# TRV_MRF49_U.net
KiCad netlist of a schematic drawn in EAGLE
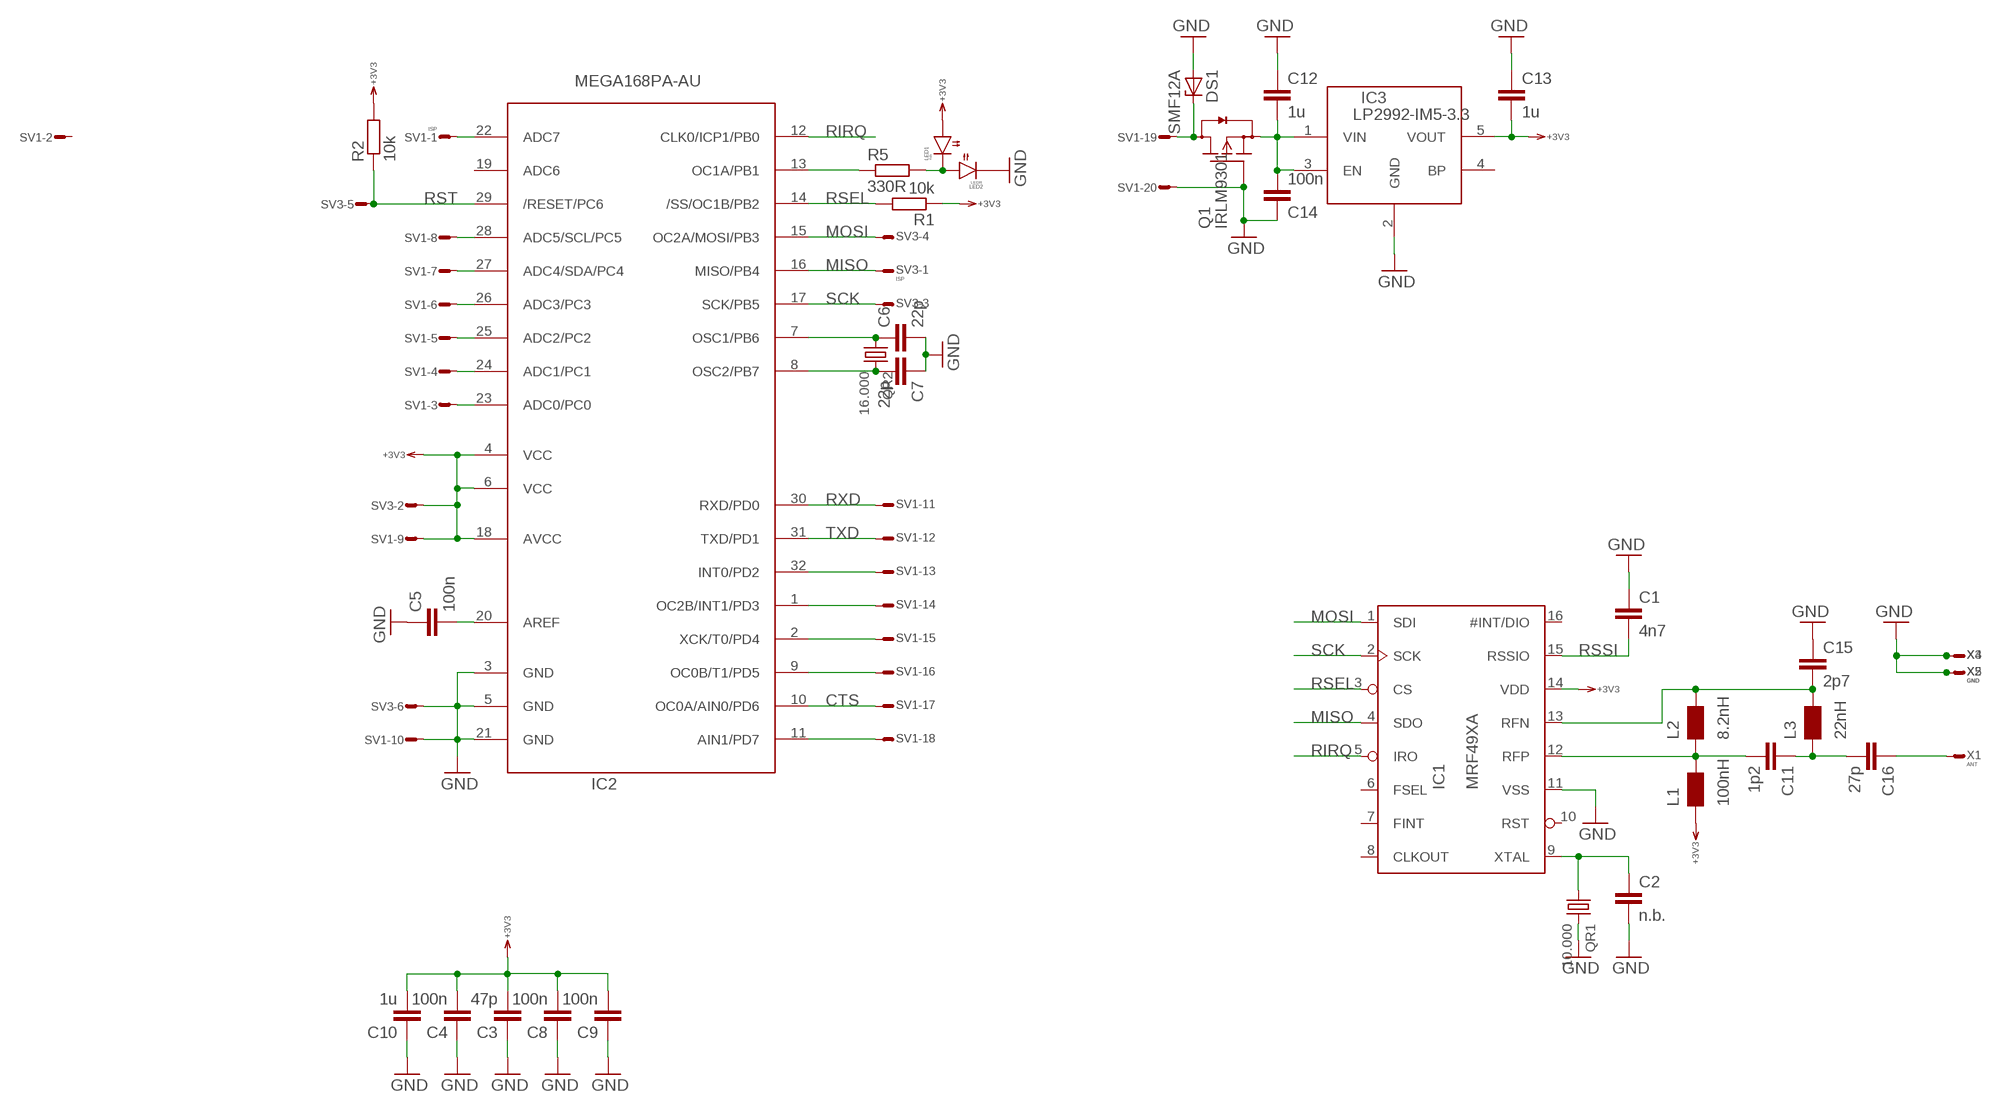
[diagram p0: schematic, sheet 1]

(export (version "E")
  (design (tool "Eeschema 10.0.6"))
  (components
    (comp (ref "C1")
      (value "4n7")
      (footprint "eagle-import:0603")
      (libsource (lib "eagle-import") (part "C0603"))
    )
    (comp (ref "C2")
      (value "n.b.")
      (footprint "eagle-import:0603")
      (libsource (lib "eagle-import") (part "C0603"))
    )
    (comp (ref "C3")
      (value "47p")
      (footprint "eagle-import:0603")
      (libsource (lib "eagle-import") (part "C0603"))
    )
    (comp (ref "C4")
      (value "100n")
      (footprint "eagle-import:0603")
      (libsource (lib "eagle-import") (part "C0603"))
    )
    (comp (ref "C5")
      (value "100n")
      (footprint "eagle-import:0603")
      (libsource (lib "eagle-import") (part "C0603"))
    )
    (comp (ref "C6")
      (value "22p")
      (footprint "eagle-import:0603")
      (libsource (lib "eagle-import") (part "C0603"))
    )
    (comp (ref "C7")
      (value "22p")
      (footprint "eagle-import:0603")
      (libsource (lib "eagle-import") (part "C0603"))
    )
    (comp (ref "C8")
      (value "100n")
      (footprint "eagle-import:0603")
      (libsource (lib "eagle-import") (part "C0603"))
    )
    (comp (ref "C9")
      (value "100n")
      (footprint "eagle-import:0603")
      (libsource (lib "eagle-import") (part "C0603"))
    )
    (comp (ref "C10")
      (value "1u")
      (footprint "eagle-import:0603")
      (libsource (lib "eagle-import") (part "C0603"))
    )
    (comp (ref "C11")
      (value "1p2")
      (footprint "eagle-import:0603")
      (libsource (lib "eagle-import") (part "C0603"))
    )
    (comp (ref "C12")
      (value "1u")
      (footprint "eagle-import:0603")
      (libsource (lib "eagle-import") (part "C0603"))
    )
    (comp (ref "C13")
      (value "1u")
      (footprint "eagle-import:0603")
      (libsource (lib "eagle-import") (part "C0603"))
    )
    (comp (ref "C14")
      (value "100n")
      (footprint "eagle-import:0603")
      (libsource (lib "eagle-import") (part "C0603"))
    )
    (comp (ref "C15")
      (value "2p7")
      (footprint "eagle-import:0603")
      (libsource (lib "eagle-import") (part "C0603"))
    )
    (comp (ref "C16")
      (value "27p")
      (footprint "eagle-import:0603")
      (libsource (lib "eagle-import") (part "C0603"))
    )
    (comp (ref "DS1")
      (value "SMF12A")
      (footprint "eagle-import:SMF")
      (libsource (lib "eagle-import") (part "TVS-DSMF"))
    )
    (comp (ref "IC1")
      (value "MRF49XA")
      (footprint "eagle-import:TSSOP16")
      (libsource (lib "eagle-import") (part "MRF49XA"))
    )
    (comp (ref "IC2")
      (value "MEGA168PA-AU")
      (footprint "eagle-import:TQFP32-08")
      (libsource (lib "eagle-import") (part "MEGA168PA"))
    )
    (comp (ref "IC3")
      (value "LP2992-IM5-3.3")
      (footprint "eagle-import:SOT23-5")
      (libsource (lib "eagle-import") (part "LDO"))
    )
    (comp (ref "L1")
      (value "100nH")
      (footprint "eagle-import:0603")
      (libsource (lib "eagle-import") (part "L0603"))
    )
    (comp (ref "L2")
      (value "8.2nH")
      (footprint "eagle-import:0603")
      (libsource (lib "eagle-import") (part "L0603"))
    )
    (comp (ref "L3")
      (value "22nH")
      (footprint "eagle-import:0603")
      (libsource (lib "eagle-import") (part "L0603"))
    )
    (comp (ref "LED1")
      (value "n.b.")
      (footprint "eagle-import:0603")
      (libsource (lib "eagle-import") (part "LED0603"))
    )
    (comp (ref "LED2")
      (value "LEDR")
      (footprint "eagle-import:0603")
      (libsource (lib "eagle-import") (part "LED0603"))
    )
    (comp (ref "Q1")
      (value "IRLM9301")
      (footprint "eagle-import:SOT23")
      (libsource (lib "eagle-import") (part "FET-PDSOT23"))
    )
    (comp (ref "QR1")
      (value "10.000")
      (footprint "eagle-import:HC49U-V")
      (libsource (lib "eagle-import") (part "Q49UV"))
    )
    (comp (ref "QR2")
      (value "16.000")
      (footprint "eagle-import:HC49U-V")
      (libsource (lib "eagle-import") (part "Q49UV"))
    )
    (comp (ref "R1")
      (value "10k")
      (footprint "eagle-import:0603")
      (libsource (lib "eagle-import") (part "R0603"))
    )
    (comp (ref "R2")
      (value "10k")
      (footprint "eagle-import:0603")
      (libsource (lib "eagle-import") (part "R0603"))
    )
    (comp (ref "R5")
      (value "330R")
      (footprint "eagle-import:0603")
      (libsource (lib "eagle-import") (part "R0603"))
    )
    (comp (ref "SV1")
      (value "ISP")
      (footprint "eagle-import:ML20")
      (libsource (lib "eagle-import") (part "ML20?E"))
    )
    (comp (ref "SV3")
      (value "ISP")
      (footprint "eagle-import:ML6")
      (libsource (lib "eagle-import") (part "ML6E"))
    )
    (comp (ref "X1")
      (value "ANT")
      (footprint "eagle-import:S2.54_1.27")
      (libsource (lib "eagle-import") (part "WIREPADS2.54/1.27"))
    )
    (comp (ref "X2")
      (value "GND")
      (footprint "eagle-import:S2.54_1.27")
      (libsource (lib "eagle-import") (part "WIREPADS2.54/1.27"))
    )
    (comp (ref "X3")
      (value "WIREPADS2.54/1.27")
      (footprint "eagle-import:S2.54_1.27")
      (libsource (lib "eagle-import") (part "WIREPADS2.54/1.27"))
    )
    (comp (ref "X4")
      (value "WIREPADS2.54/1.27")
      (footprint "eagle-import:S2.54_1.27")
      (libsource (lib "eagle-import") (part "WIREPADS2.54/1.27"))
    )
    (comp (ref "X5")
      (value "GND")
      (footprint "eagle-import:S2.54_1.27")
      (libsource (lib "eagle-import") (part "WIREPADS2.54/1.27"))
    )
  )
  (nets
    (net (code "1") (name "+3V3") (class "Default")
      (node (ref "C10") (pin "2") (pinfunction "2_2") (pintype "passive"))
      (node (ref "C13") (pin "2") (pinfunction "2_2") (pintype "passive"))
      (node (ref "C3") (pin "2") (pinfunction "2_2") (pintype "passive"))
      (node (ref "C4") (pin "2") (pinfunction "2_2") (pintype "passive"))
      (node (ref "C8") (pin "2") (pinfunction "2_2") (pintype "passive"))
      (node (ref "C9") (pin "2") (pinfunction "2_2") (pintype "passive"))
      (node (ref "IC1") (pin "14") (pinfunction "VDD_14") (pintype "input"))
      (node (ref "IC2") (pin "18") (pinfunction "AVCC_18") (pintype "bidirectional"))
      (node (ref "IC2") (pin "4") (pinfunction "VCC_4") (pintype "bidirectional"))
      (node (ref "IC2") (pin "6") (pinfunction "VCC_6") (pintype "bidirectional"))
      (node (ref "IC3") (pin "5") (pinfunction "VOUT_5") (pintype "bidirectional"))
      (node (ref "L1") (pin "1") (pinfunction "1_1") (pintype "passive"))
      (node (ref "LED1") (pin "1") (pinfunction "A_1") (pintype "bidirectional"))
      (node (ref "R1") (pin "1") (pinfunction "1_1") (pintype "passive"))
      (node (ref "R2") (pin "2") (pinfunction "2_2") (pintype "passive"))
      (node (ref "SV1") (pin "9") (pinfunction "S_9") (pintype "passive"))
      (node (ref "SV3") (pin "2") (pinfunction "S_2") (pintype "passive"))
    )
    (net (code "2") (name "/CTS") (class "Default")
      (node (ref "IC2") (pin "10") (pinfunction "OC0A/AIN0/PD6_10") (pintype "bidirectional"))
      (node (ref "SV1") (pin "17") (pinfunction "S_17") (pintype "passive"))
    )
    (net (code "3") (name "/MISO") (class "Default")
      (node (ref "IC1") (pin "4") (pinfunction "SDO_4") (pintype "output"))
      (node (ref "IC2") (pin "16") (pinfunction "MISO/PB4_16") (pintype "bidirectional"))
      (node (ref "SV3") (pin "1") (pinfunction "S_1") (pintype "passive"))
    )
    (net (code "4") (name "/MOSI") (class "Default")
      (node (ref "IC1") (pin "1") (pinfunction "SDI_1") (pintype "input"))
      (node (ref "IC2") (pin "15") (pinfunction "OC2A/MOSI/PB3_15") (pintype "bidirectional"))
      (node (ref "SV3") (pin "4") (pinfunction "S_4") (pintype "passive"))
    )
    (net (code "5") (name "/RIRQ") (class "Default")
      (node (ref "IC1") (pin "5") (pinfunction "IRO_5") (pintype "output"))
      (node (ref "IC2") (pin "12") (pinfunction "CLK0/ICP1/PB0_12") (pintype "bidirectional"))
    )
    (net (code "6") (name "/RSEL") (class "Default")
      (node (ref "IC1") (pin "3") (pinfunction "CS_3") (pintype "input"))
      (node (ref "IC2") (pin "14") (pinfunction "/SS/OC1B/PB2_14") (pintype "bidirectional"))
      (node (ref "R1") (pin "2") (pinfunction "2_2") (pintype "passive"))
    )
    (net (code "7") (name "/RSSI") (class "Default")
      (node (ref "C1") (pin "2") (pinfunction "2_2") (pintype "passive"))
      (node (ref "IC1") (pin "15") (pinfunction "RSSIO_15") (pintype "bidirectional"))
    )
    (net (code "8") (name "/RST") (class "Default")
      (node (ref "IC2") (pin "29") (pinfunction "/RESET/PC6_29") (pintype "bidirectional"))
      (node (ref "R2") (pin "1") (pinfunction "1_1") (pintype "passive"))
      (node (ref "SV3") (pin "5") (pinfunction "S_5") (pintype "passive"))
    )
    (net (code "9") (name "/RXD") (class "Default")
      (node (ref "IC2") (pin "30") (pinfunction "RXD/PD0_30") (pintype "bidirectional"))
      (node (ref "SV1") (pin "11") (pinfunction "S_11") (pintype "passive"))
    )
    (net (code "10") (name "/SCK") (class "Default")
      (node (ref "IC1") (pin "2") (pinfunction "SCK_2") (pintype "input"))
      (node (ref "IC2") (pin "17") (pinfunction "SCK/PB5_17") (pintype "bidirectional"))
      (node (ref "SV3") (pin "3") (pinfunction "S_3") (pintype "passive"))
    )
    (net (code "11") (name "/TXD") (class "Default")
      (node (ref "IC2") (pin "31") (pinfunction "TXD/PD1_31") (pintype "bidirectional"))
      (node (ref "SV1") (pin "12") (pinfunction "S_12") (pintype "passive"))
    )
    (net (code "12") (name "GND") (class "Default")
      (node (ref "C1") (pin "1") (pinfunction "1_1") (pintype "passive"))
      (node (ref "C10") (pin "1") (pinfunction "1_1") (pintype "passive"))
      (node (ref "C12") (pin "1") (pinfunction "1_1") (pintype "passive"))
      (node (ref "C13") (pin "1") (pinfunction "1_1") (pintype "passive"))
      (node (ref "C14") (pin "1") (pinfunction "1_1") (pintype "passive"))
      (node (ref "C15") (pin "1") (pinfunction "1_1") (pintype "passive"))
      (node (ref "C2") (pin "2") (pinfunction "2_2") (pintype "passive"))
      (node (ref "C3") (pin "1") (pinfunction "1_1") (pintype "passive"))
      (node (ref "C4") (pin "1") (pinfunction "1_1") (pintype "passive"))
      (node (ref "C5") (pin "1") (pinfunction "1_1") (pintype "passive"))
      (node (ref "C6") (pin "2") (pinfunction "2_2") (pintype "passive"))
      (node (ref "C7") (pin "1") (pinfunction "1_1") (pintype "passive"))
      (node (ref "C8") (pin "1") (pinfunction "1_1") (pintype "passive"))
      (node (ref "C9") (pin "1") (pinfunction "1_1") (pintype "passive"))
      (node (ref "DS1") (pin "A") (pinfunction "A_A") (pintype "passive"))
      (node (ref "IC1") (pin "11") (pinfunction "VSS_11") (pintype "input"))
      (node (ref "IC2") (pin "21") (pinfunction "GND_21") (pintype "bidirectional"))
      (node (ref "IC2") (pin "3") (pinfunction "GND_3") (pintype "bidirectional"))
      (node (ref "IC2") (pin "5") (pinfunction "GND_5") (pintype "bidirectional"))
      (node (ref "IC3") (pin "2") (pinfunction "GND_2") (pintype "bidirectional"))
      (node (ref "LED2") (pin "2") (pinfunction "C_2") (pintype "bidirectional"))
      (node (ref "Q1") (pin "1") (pinfunction "G_1") (pintype "passive"))
      (node (ref "QR1") (pin "2") (pinfunction "2_2") (pintype "passive"))
      (node (ref "SV1") (pin "10") (pinfunction "S_10") (pintype "passive"))
      (node (ref "SV1") (pin "20") (pinfunction "S_20") (pintype "passive"))
      (node (ref "SV3") (pin "6") (pinfunction "S_6") (pintype "passive"))
      (node (ref "X2") (pin "1") (pinfunction "S_1") (pintype "passive"))
      (node (ref "X3") (pin "1") (pinfunction "S_1") (pintype "passive"))
      (node (ref "X4") (pin "1") (pinfunction "S_1") (pintype "passive"))
      (node (ref "X5") (pin "1") (pinfunction "S_1") (pintype "passive"))
    )
    (net (code "13") (name "Net-(C11-Pad1)") (class "Default")
      (node (ref "C11") (pin "1") (pinfunction "1_1") (pintype "passive"))
      (node (ref "C16") (pin "2") (pinfunction "2_2") (pintype "passive"))
      (node (ref "L3") (pin "1") (pinfunction "1_1") (pintype "passive"))
    )
    (net (code "14") (name "Net-(IC1-RFN)") (class "Default")
      (node (ref "C15") (pin "2") (pinfunction "2_2") (pintype "passive"))
      (node (ref "IC1") (pin "13") (pinfunction "RFN_13") (pintype "bidirectional"))
      (node (ref "L2") (pin "2") (pinfunction "2_2") (pintype "passive"))
      (node (ref "L3") (pin "2") (pinfunction "2_2") (pintype "passive"))
    )
    (net (code "15") (name "Net-(IC1-RFP)") (class "Default")
      (node (ref "C11") (pin "2") (pinfunction "2_2") (pintype "passive"))
      (node (ref "IC1") (pin "12") (pinfunction "RFP_12") (pintype "bidirectional"))
      (node (ref "L1") (pin "2") (pinfunction "2_2") (pintype "passive"))
      (node (ref "L2") (pin "1") (pinfunction "1_1") (pintype "passive"))
    )
    (net (code "16") (name "Net-(IC1-XTAL)") (class "Default")
      (node (ref "C2") (pin "1") (pinfunction "1_1") (pintype "passive"))
      (node (ref "IC1") (pin "9") (pinfunction "XTAL_9") (pintype "input"))
      (node (ref "QR1") (pin "1") (pinfunction "1_1") (pintype "passive"))
    )
    (net (code "17") (name "Net-(IC2-ADC0{slash}PC0)") (class "Default")
      (node (ref "IC2") (pin "23") (pinfunction "ADC0/PC0_23") (pintype "bidirectional"))
      (node (ref "SV1") (pin "3") (pinfunction "S_3") (pintype "passive"))
    )
    (net (code "18") (name "Net-(IC2-ADC1{slash}PC1)") (class "Default")
      (node (ref "IC2") (pin "24") (pinfunction "ADC1/PC1_24") (pintype "bidirectional"))
      (node (ref "SV1") (pin "4") (pinfunction "S_4") (pintype "passive"))
    )
    (net (code "19") (name "Net-(IC2-ADC2{slash}PC2)") (class "Default")
      (node (ref "IC2") (pin "25") (pinfunction "ADC2/PC2_25") (pintype "bidirectional"))
      (node (ref "SV1") (pin "5") (pinfunction "S_5") (pintype "passive"))
    )
    (net (code "20") (name "Net-(IC2-ADC3{slash}PC3)") (class "Default")
      (node (ref "IC2") (pin "26") (pinfunction "ADC3/PC3_26") (pintype "bidirectional"))
      (node (ref "SV1") (pin "6") (pinfunction "S_6") (pintype "passive"))
    )
    (net (code "21") (name "Net-(IC2-ADC4{slash}SDA{slash}PC4)") (class "Default")
      (node (ref "IC2") (pin "27") (pinfunction "ADC4/SDA/PC4_27") (pintype "bidirectional"))
      (node (ref "SV1") (pin "7") (pinfunction "S_7") (pintype "passive"))
    )
    (net (code "22") (name "Net-(IC2-ADC5{slash}SCL{slash}PC5)") (class "Default")
      (node (ref "IC2") (pin "28") (pinfunction "ADC5/SCL/PC5_28") (pintype "bidirectional"))
      (node (ref "SV1") (pin "8") (pinfunction "S_8") (pintype "passive"))
    )
    (net (code "23") (name "Net-(IC2-ADC7)") (class "Default")
      (node (ref "IC2") (pin "22") (pinfunction "ADC7_22") (pintype "bidirectional"))
      (node (ref "SV1") (pin "1") (pinfunction "S_1") (pintype "passive"))
    )
    (net (code "24") (name "Net-(IC2-AIN1{slash}PD7)") (class "Default")
      (node (ref "IC2") (pin "11") (pinfunction "AIN1/PD7_11") (pintype "bidirectional"))
      (node (ref "SV1") (pin "18") (pinfunction "S_18") (pintype "passive"))
    )
    (net (code "25") (name "Net-(IC2-AREF)") (class "Default")
      (node (ref "C5") (pin "2") (pinfunction "2_2") (pintype "passive"))
      (node (ref "IC2") (pin "20") (pinfunction "AREF_20") (pintype "bidirectional"))
    )
    (net (code "26") (name "Net-(IC2-INT0{slash}PD2)") (class "Default")
      (node (ref "IC2") (pin "32") (pinfunction "INT0/PD2_32") (pintype "bidirectional"))
      (node (ref "SV1") (pin "13") (pinfunction "S_13") (pintype "passive"))
    )
    (net (code "27") (name "Net-(IC2-OC0B{slash}T1{slash}PD5)") (class "Default")
      (node (ref "IC2") (pin "9") (pinfunction "OC0B/T1/PD5_9") (pintype "bidirectional"))
      (node (ref "SV1") (pin "16") (pinfunction "S_16") (pintype "passive"))
    )
    (net (code "28") (name "Net-(IC2-OC1A{slash}PB1)") (class "Default")
      (node (ref "IC2") (pin "13") (pinfunction "OC1A/PB1_13") (pintype "bidirectional"))
      (node (ref "R5") (pin "1") (pinfunction "1_1") (pintype "passive"))
    )
    (net (code "29") (name "Net-(IC2-OC2B{slash}INT1{slash}PD3)") (class "Default")
      (node (ref "IC2") (pin "1") (pinfunction "OC2B/INT1/PD3_1") (pintype "bidirectional"))
      (node (ref "SV1") (pin "14") (pinfunction "S_14") (pintype "passive"))
    )
    (net (code "30") (name "Net-(IC2-OSC1{slash}PB6)") (class "Default")
      (node (ref "C6") (pin "1") (pinfunction "1_1") (pintype "passive"))
      (node (ref "IC2") (pin "7") (pinfunction "OSC1/PB6_7") (pintype "bidirectional"))
      (node (ref "QR2") (pin "1") (pinfunction "1_1") (pintype "passive"))
    )
    (net (code "31") (name "Net-(IC2-OSC2{slash}PB7)") (class "Default")
      (node (ref "C7") (pin "2") (pinfunction "2_2") (pintype "passive"))
      (node (ref "IC2") (pin "8") (pinfunction "OSC2/PB7_8") (pintype "bidirectional"))
      (node (ref "QR2") (pin "2") (pinfunction "2_2") (pintype "passive"))
    )
    (net (code "32") (name "Net-(IC2-XCK{slash}T0{slash}PD4)") (class "Default")
      (node (ref "IC2") (pin "2") (pinfunction "XCK/T0/PD4_2") (pintype "bidirectional"))
      (node (ref "SV1") (pin "15") (pinfunction "S_15") (pintype "passive"))
    )
    (net (code "33") (name "Net-(IC3-EN)") (class "Default")
      (node (ref "C12") (pin "2") (pinfunction "2_2") (pintype "passive"))
      (node (ref "C14") (pin "2") (pinfunction "2_2") (pintype "passive"))
      (node (ref "IC3") (pin "1") (pinfunction "VIN_1") (pintype "bidirectional"))
      (node (ref "IC3") (pin "3") (pinfunction "EN_3") (pintype "bidirectional"))
      (node (ref "Q1") (pin "2") (pinfunction "S_2") (pintype "passive"))
    )
    (net (code "34") (name "Net-(LED1-C)") (class "Default")
      (node (ref "LED1") (pin "2") (pinfunction "C_2") (pintype "bidirectional"))
      (node (ref "LED2") (pin "1") (pinfunction "A_1") (pintype "bidirectional"))
      (node (ref "R5") (pin "2") (pinfunction "2_2") (pintype "passive"))
    )
    (net (code "35") (name "Net-(Q1-D)") (class "Default")
      (node (ref "DS1") (pin "C") (pinfunction "C_C") (pintype "passive"))
      (node (ref "Q1") (pin "3") (pinfunction "D_3") (pintype "passive"))
      (node (ref "SV1") (pin "19") (pinfunction "S_19") (pintype "passive"))
    )
    (net (code "36") (name "Net-(X1-S)") (class "Default")
      (node (ref "C16") (pin "1") (pinfunction "1_1") (pintype "passive"))
      (node (ref "X1") (pin "1") (pinfunction "S_1") (pintype "passive"))
    )
    (net (code "37") (name "unconnected-(IC1-#INT{slash}DIO-Pad16)") (class "Default")
      (node (ref "IC1") (pin "16") (pinfunction "#INT/DIO_16") (pintype "bidirectional"))
    )
    (net (code "38") (name "unconnected-(IC1-CLKOUT-Pad8)") (class "Default")
      (node (ref "IC1") (pin "8") (pinfunction "CLKOUT_8") (pintype "output"))
    )
    (net (code "39") (name "unconnected-(IC1-FINT-Pad7)") (class "Default")
      (node (ref "IC1") (pin "7") (pinfunction "FINT_7") (pintype "bidirectional"))
    )
    (net (code "40") (name "unconnected-(IC1-FSEL-Pad6)") (class "Default")
      (node (ref "IC1") (pin "6") (pinfunction "FSEL_6") (pintype "bidirectional"))
    )
    (net (code "41") (name "unconnected-(IC1-RST-Pad10)") (class "Default")
      (node (ref "IC1") (pin "10") (pinfunction "RST_10") (pintype "bidirectional"))
    )
    (net (code "42") (name "unconnected-(IC2-ADC6-Pad19)") (class "Default")
      (node (ref "IC2") (pin "19") (pinfunction "ADC6_19") (pintype "bidirectional"))
    )
    (net (code "43") (name "unconnected-(IC3-BP-Pad4)") (class "Default")
      (node (ref "IC3") (pin "4") (pinfunction "BP_4") (pintype "bidirectional"))
    )
    (net (code "44") (name "unconnected-(SV1L-S-Pad2)") (class "Default")
      (node (ref "SV1") (pin "2") (pinfunction "S_2") (pintype "passive"))
    )
  )
)
